# picoAva-Rev2.net
KiCad netlist of a schematic drawn in EAGLE
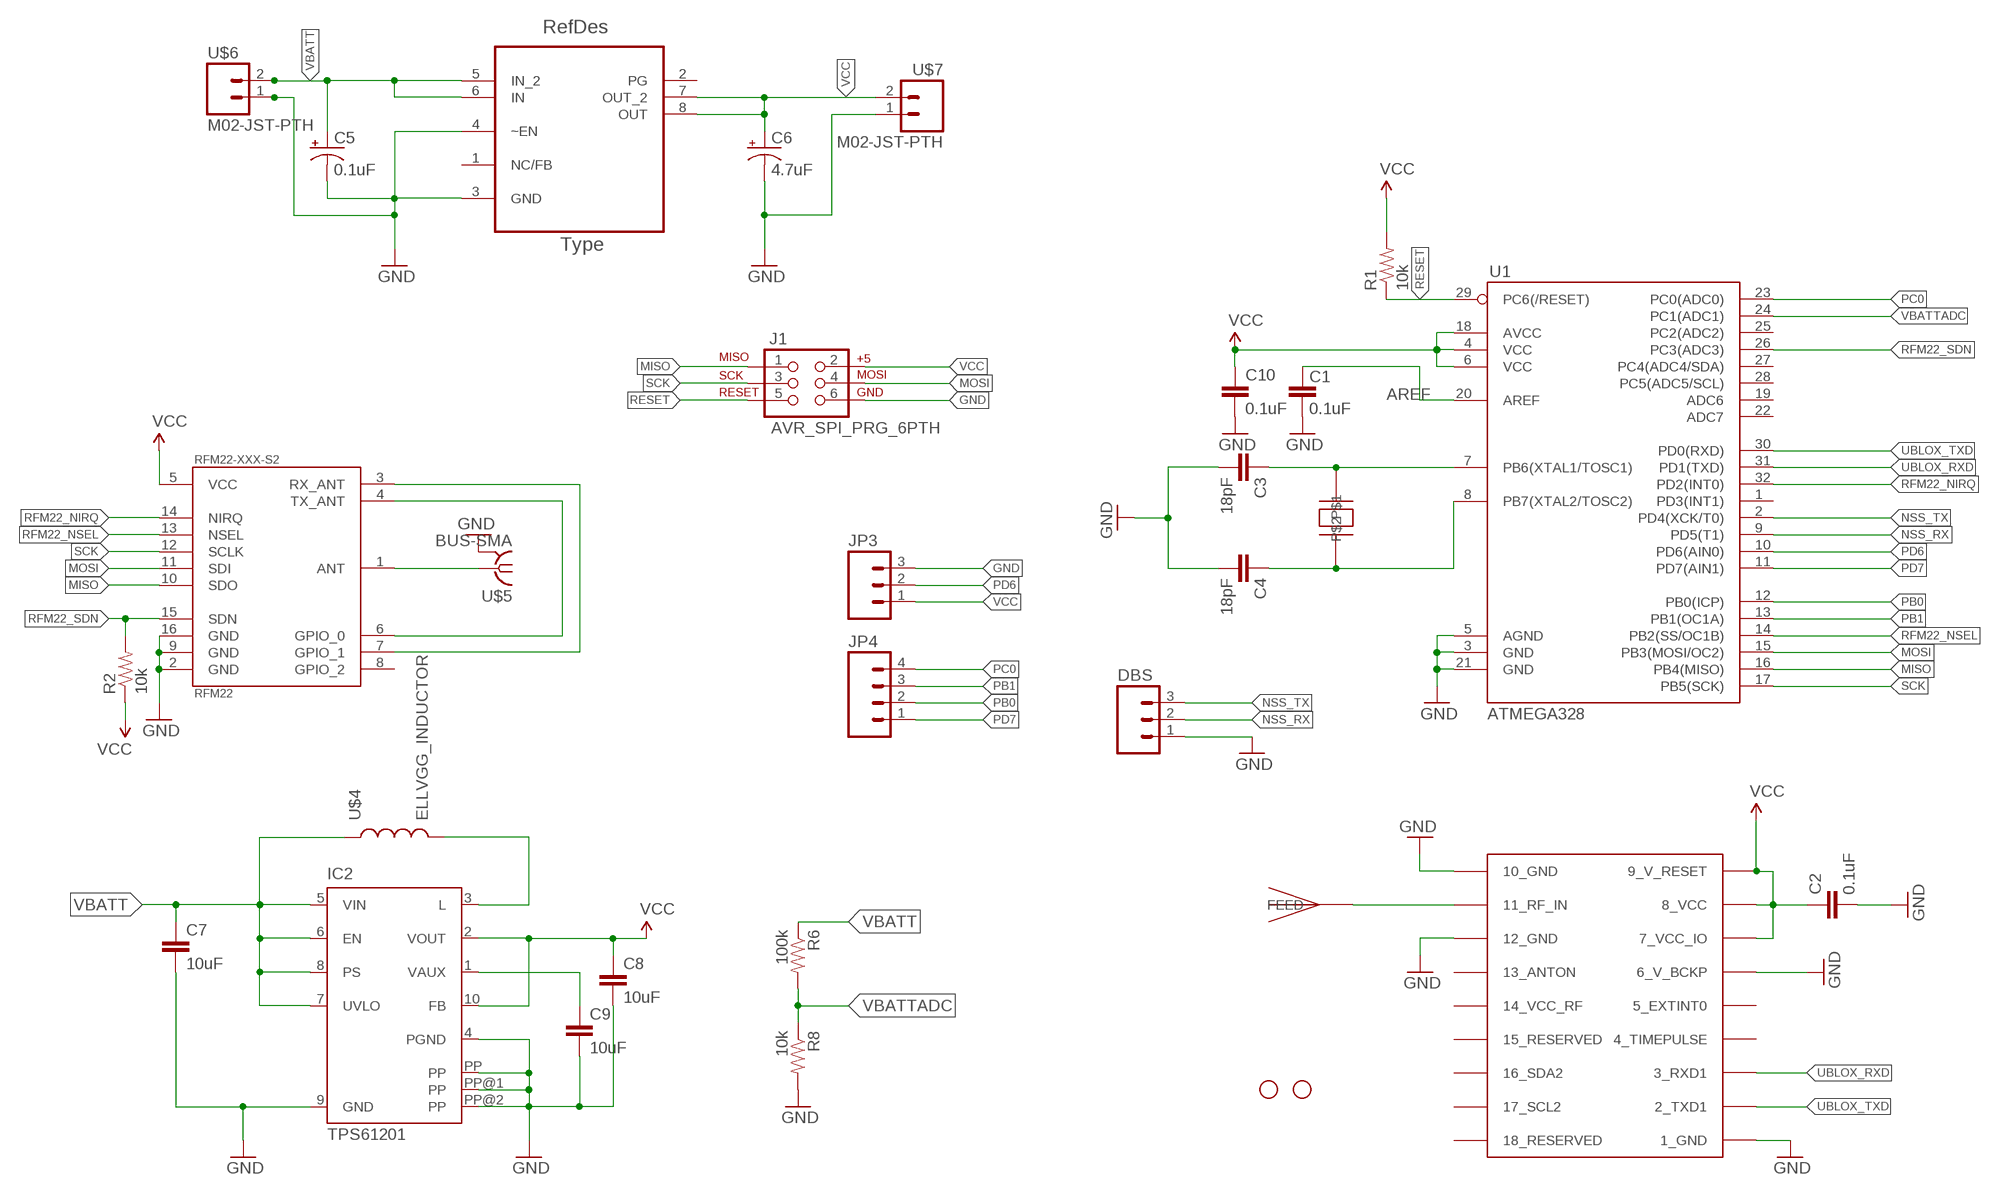
[diagram p0: schematic, sheet 1]

(export (version "E")
  (design (tool "Eeschema 10.0.6"))
  (components
    (comp (ref "C1")
      (value "0.1uF")
      (footprint "eagle-import:0402-CAP")
      (libsource (lib "eagle-import") (part "CAP0402-CAP"))
    )
    (comp (ref "C2")
      (value "0.1uF")
      (footprint "eagle-import:0402-CAP")
      (libsource (lib "eagle-import") (part "CAP0402-CAP"))
    )
    (comp (ref "C3")
      (value "18pF")
      (footprint "eagle-import:0402-CAP")
      (libsource (lib "eagle-import") (part "CAP0402-CAP"))
    )
    (comp (ref "C4")
      (value "18pF")
      (footprint "eagle-import:0402-CAP")
      (libsource (lib "eagle-import") (part "CAP0402-CAP"))
    )
    (comp (ref "C5")
      (value "0.1uF")
      (footprint "eagle-import:EIA3216-KIT")
      (libsource (lib "eagle-import") (part "CAP_POL1206-KIT"))
    )
    (comp (ref "C6")
      (value "4.7uF")
      (footprint "eagle-import:EIA3216-KIT")
      (libsource (lib "eagle-import") (part "CAP_POL1206-KIT"))
    )
    (comp (ref "C7")
      (value "10uF")
      (footprint "eagle-import:1206")
      (libsource (lib "eagle-import") (part "CAP1206"))
    )
    (comp (ref "C8")
      (value "10uF")
      (footprint "eagle-import:1206")
      (libsource (lib "eagle-import") (part "CAP1206"))
    )
    (comp (ref "C9")
      (value "10uF")
      (footprint "eagle-import:1206")
      (libsource (lib "eagle-import") (part "CAP1206"))
    )
    (comp (ref "C10")
      (value "0.1uF")
      (footprint "eagle-import:0402-CAP")
      (libsource (lib "eagle-import") (part "CAP0402-CAP"))
    )
    (comp (ref "DBS")
      (value "M03PTH")
      (footprint "eagle-import:1X03")
      (libsource (lib "eagle-import") (part "M03PTH"))
    )
    (comp (ref "IC2")
      (value "TPS61201")
      (footprint "eagle-import:S-PDSO-N10")
      (fields (field (name "MPN") "TPS61201DRCT"))
      (libsource (lib "eagle-import") (part "TPS61201"))
    )
    (comp (ref "J1")
      (value "AVR_SPI_PRG_6PTH")
      (footprint "eagle-import:2X3")
      (libsource (lib "eagle-import") (part "AVR_SPI_PRG_6PTH"))
    )
    (comp (ref "JP1")
      (value "STAND-OFF")
      (footprint "eagle-import:STAND-OFF")
      (libsource (lib "eagle-import") (part "STAND-OFF"))
    )
    (comp (ref "JP2")
      (value "STAND-OFF")
      (footprint "eagle-import:STAND-OFF")
      (libsource (lib "eagle-import") (part "STAND-OFF"))
    )
    (comp (ref "JP3")
      (value "M03PTH")
      (footprint "eagle-import:1X03")
      (libsource (lib "eagle-import") (part "M03PTH"))
    )
    (comp (ref "JP4")
      (value "M04PTH")
      (footprint "eagle-import:1X04")
      (libsource (lib "eagle-import") (part "M04PTH"))
    )
    (comp (ref "R1")
      (value "10k")
      (footprint "eagle-import:0402-RES")
      (libsource (lib "eagle-import") (part "RESISTOR0402-RES"))
    )
    (comp (ref "R2")
      (value "10k")
      (footprint "eagle-import:0402-RES")
      (libsource (lib "eagle-import") (part "RESISTOR0402-RES"))
    )
    (comp (ref "R6")
      (value "100k")
      (footprint "eagle-import:0402-RES")
      (libsource (lib "eagle-import") (part "RESISTOR0402-RES"))
    )
    (comp (ref "R8")
      (value "10k")
      (footprint "eagle-import:0402-RES")
      (libsource (lib "eagle-import") (part "RESISTOR0402-RES"))
    )
    (comp (ref "RFM22-XXX-S2")
      (value "RFM22")
      (footprint "eagle-import:RFM22-XXX-S2")
      (libsource (lib "eagle-import") (part "RFM22"))
    )
    (comp (ref "U$1")
      (value "UBLOX_MAX-6")
      (footprint "eagle-import:UBLOX_MAX-6")
      (libsource (lib "eagle-import") (part "UBLOX_MAX-6"))
    )
    (comp (ref "U$2")
      (value "ABRACON_ABM3_CRYSTAL")
      (footprint "eagle-import:ABRACON_ABM3_CRYSTAL")
      (libsource (lib "eagle-import") (part "ABRACON_ABM3_CRYSTAL"))
    )
    (comp (ref "U$3")
      (value "JTI_ANTENNA-1575AT43A40")
      (footprint "eagle-import:JTI_ANTENNA-1575AT43A40")
      (libsource (lib "eagle-import") (part "JTI_ANTENNA-1575AT43A40"))
    )
    (comp (ref "U$4")
      (value "ELLVGG_INDUCTOR")
      (footprint "eagle-import:ELLVGG_INDUCTOR")
      (libsource (lib "eagle-import") (part "ELLVGG_INDUCTOR"))
    )
    (comp (ref "U$5")
      (value "BUS-SMA")
      (footprint "eagle-import:BUS-SMA")
      (libsource (lib "eagle-import") (part "BUS-SMA"))
    )
    (comp (ref "U$6")
      (value "M02-JST-PTH")
      (footprint "eagle-import:M02-JST-PTH")
      (libsource (lib "eagle-import") (part "M02-JST-PTH"))
    )
    (comp (ref "U$7")
      (value "M02-JST-PTH")
      (footprint "eagle-import:M02-JST-PTH")
      (libsource (lib "eagle-import") (part "M02-JST-PTH"))
    )
    (comp (ref "U1")
      (value "ATMEGA328")
      (footprint "eagle-import:TQFP32-08")
      (libsource (lib "eagle-import") (part "ATMEGA168"))
    )
    (comp (ref "U2")
      (value "TPS76633D")
      (footprint "eagle-import:SOIC127P600X175-8N")
      (libsource (lib "eagle-import") (part "TPS76633D"))
    )
  )
  (nets
    (net (code "1") (name "/AREF") (class "Default")
      (node (ref "C1") (pin "2") (pinfunction "2_2") (pintype "passive"))
      (node (ref "U1") (pin "20") (pinfunction "AREF_20") (pintype "bidirectional"))
    )
    (net (code "2") (name "GND") (class "Default")
      (node (ref "C1") (pin "1") (pinfunction "1_1") (pintype "passive"))
      (node (ref "C10") (pin "2") (pinfunction "2_2") (pintype "passive"))
      (node (ref "C2") (pin "2") (pinfunction "2_2") (pintype "passive"))
      (node (ref "C3") (pin "2") (pinfunction "2_2") (pintype "passive"))
      (node (ref "C4") (pin "2") (pinfunction "2_2") (pintype "passive"))
      (node (ref "C5") (pin "C") (pinfunction "-_C") (pintype "passive"))
      (node (ref "C6") (pin "C") (pinfunction "-_C") (pintype "passive"))
      (node (ref "C7") (pin "2") (pinfunction "2_2") (pintype "passive"))
      (node (ref "C8") (pin "2") (pinfunction "2_2") (pintype "passive"))
      (node (ref "C9") (pin "2") (pinfunction "2_2") (pintype "passive"))
      (node (ref "DBS") (pin "1") (pinfunction "1_1") (pintype "passive"))
      (node (ref "IC2") (pin "4") (pinfunction "PGND_4") (pintype "power_in"))
      (node (ref "IC2") (pin "9") (pinfunction "GND_9") (pintype "power_in"))
      (node (ref "IC2") (pin "PP") (pinfunction "PP_PP") (pintype "power_in"))
      (node (ref "IC2") (pin "PP@1") (pinfunction "PP_PP@1") (pintype "power_in"))
      (node (ref "IC2") (pin "PP@2") (pinfunction "PP_PP@2") (pintype "power_in"))
      (node (ref "J1") (pin "6") (pinfunction "6_6") (pintype "passive"))
      (node (ref "JP3") (pin "3") (pinfunction "3_3") (pintype "passive"))
      (node (ref "R8") (pin "2") (pinfunction "2_2") (pintype "passive"))
      (node (ref "RFM22-XXX-S2") (pin "16") (pinfunction "GND_16") (pintype "power_in"))
      (node (ref "RFM22-XXX-S2") (pin "2") (pinfunction "GND_2") (pintype "power_in"))
      (node (ref "RFM22-XXX-S2") (pin "9") (pinfunction "GND_9") (pintype "power_in"))
      (node (ref "U$1") (pin "10_GND") (pinfunction "10_GND_10_GND") (pintype "bidirectional"))
      (node (ref "U$1") (pin "12_GND") (pinfunction "12_GND_12_GND") (pintype "bidirectional"))
      (node (ref "U$1") (pin "1_GND") (pinfunction "1_GND_1_GND") (pintype "bidirectional"))
      (node (ref "U$1") (pin "6_V_BCKP") (pinfunction "6_V_BCKP_6_V_BCKP") (pintype "bidirectional"))
      (node (ref "U$5") (pin "2") (pinfunction "GND_2") (pintype "power_in"))
      (node (ref "U$5") (pin "3") (pinfunction "GND_3") (pintype "power_in"))
      (node (ref "U$5") (pin "4") (pinfunction "GND_4") (pintype "power_in"))
      (node (ref "U$5") (pin "5") (pinfunction "GND_5") (pintype "power_in"))
      (node (ref "U$6") (pin "1") (pinfunction "1_1") (pintype "passive"))
      (node (ref "U$7") (pin "1") (pinfunction "1_1") (pintype "passive"))
      (node (ref "U1") (pin "21") (pinfunction "GND_21") (pintype "bidirectional"))
      (node (ref "U1") (pin "3") (pinfunction "GND_3") (pintype "bidirectional"))
      (node (ref "U1") (pin "5") (pinfunction "AGND_5") (pintype "bidirectional"))
      (node (ref "U2") (pin "3") (pinfunction "GND_3") (pintype "passive"))
      (node (ref "U2") (pin "4") (pinfunction "~{EN}_4") (pintype "input"))
    )
    (net (code "3") (name "MISO") (class "Default")
      (node (ref "J1") (pin "1") (pinfunction "1_1") (pintype "passive"))
      (node (ref "RFM22-XXX-S2") (pin "10") (pinfunction "SDO_10") (pintype "output"))
      (node (ref "U1") (pin "16") (pinfunction "PB4(MISO)_16") (pintype "bidirectional"))
    )
    (net (code "4") (name "MOSI") (class "Default")
      (node (ref "J1") (pin "4") (pinfunction "4_4") (pintype "passive"))
      (node (ref "RFM22-XXX-S2") (pin "11") (pinfunction "SDI_11") (pintype "input"))
      (node (ref "U1") (pin "15") (pinfunction "PB3(MOSI/OC2)_15") (pintype "bidirectional"))
    )
    (net (code "5") (name "NSS_RX") (class "Default")
      (node (ref "DBS") (pin "2") (pinfunction "2_2") (pintype "passive"))
      (node (ref "U1") (pin "9") (pinfunction "PD5(T1)_9") (pintype "bidirectional"))
    )
    (net (code "6") (name "NSS_TX") (class "Default")
      (node (ref "DBS") (pin "3") (pinfunction "3_3") (pintype "passive"))
      (node (ref "U1") (pin "2") (pinfunction "PD4(XCK/T0)_2") (pintype "bidirectional"))
    )
    (net (code "7") (name "Net-(IC2-L)") (class "Default")
      (node (ref "IC2") (pin "3") (pinfunction "L_3") (pintype "input"))
      (node (ref "U$4") (pin "P$2") (pinfunction "2_P$2") (pintype "passive"))
    )
    (net (code "8") (name "Net-(IC2-VAUX)") (class "Default")
      (node (ref "C9") (pin "1") (pinfunction "1_1") (pintype "passive"))
      (node (ref "IC2") (pin "1") (pinfunction "VAUX_1") (pintype "bidirectional"))
    )
    (net (code "9") (name "Net-(RFM22-XXX-S2-ANT)") (class "Default")
      (node (ref "RFM22-XXX-S2") (pin "1") (pinfunction "ANT_1") (pintype "bidirectional"))
      (node (ref "U$5") (pin "1") (pinfunction "1_1") (pintype "passive"))
    )
    (net (code "10") (name "Net-(RFM22-XXX-S2-GPIO_0)") (class "Default")
      (node (ref "RFM22-XXX-S2") (pin "4") (pinfunction "TX_ANT_4") (pintype "input"))
      (node (ref "RFM22-XXX-S2") (pin "6") (pinfunction "GPIO_0_6") (pintype "bidirectional"))
    )
    (net (code "11") (name "Net-(RFM22-XXX-S2-GPIO_1)") (class "Default")
      (node (ref "RFM22-XXX-S2") (pin "3") (pinfunction "RX_ANT_3") (pintype "input"))
      (node (ref "RFM22-XXX-S2") (pin "7") (pinfunction "GPIO_1_7") (pintype "bidirectional"))
    )
    (net (code "12") (name "Net-(U$1-Pad11_RF_IN)") (class "Default")
      (node (ref "U$1") (pin "11_RF_IN") (pinfunction "11_RF_IN_11_RF_IN") (pintype "bidirectional"))
      (node (ref "U$3") (pin "FEED") (pinfunction "FEED_FEED") (pintype "bidirectional"))
    )
    (net (code "13") (name "Net-(U1-PB6(XTAL1{slash}TOSC1))") (class "Default")
      (node (ref "C3") (pin "1") (pinfunction "1_1") (pintype "passive"))
      (node (ref "U$2") (pin "P$2") (pinfunction "P$2_P$2") (pintype "bidirectional"))
      (node (ref "U1") (pin "7") (pinfunction "PB6(XTAL1/TOSC1)_7") (pintype "bidirectional"))
    )
    (net (code "14") (name "Net-(U1-PB7(XTAL2{slash}TOSC2))") (class "Default")
      (node (ref "C4") (pin "1") (pinfunction "1_1") (pintype "passive"))
      (node (ref "U$2") (pin "P$1") (pinfunction "P$1_P$1") (pintype "bidirectional"))
      (node (ref "U1") (pin "8") (pinfunction "PB7(XTAL2/TOSC2)_8") (pintype "bidirectional"))
    )
    (net (code "15") (name "PB0") (class "Default")
      (node (ref "JP4") (pin "2") (pinfunction "2_2") (pintype "passive"))
      (node (ref "U1") (pin "12") (pinfunction "PB0(ICP)_12") (pintype "bidirectional"))
    )
    (net (code "16") (name "PB1") (class "Default")
      (node (ref "JP4") (pin "3") (pinfunction "3_3") (pintype "passive"))
      (node (ref "U1") (pin "13") (pinfunction "PB1(OC1A)_13") (pintype "bidirectional"))
    )
    (net (code "17") (name "PC0") (class "Default")
      (node (ref "JP4") (pin "4") (pinfunction "4_4") (pintype "passive"))
      (node (ref "U1") (pin "23") (pinfunction "PC0(ADC0)_23") (pintype "bidirectional"))
    )
    (net (code "18") (name "PD6") (class "Default")
      (node (ref "JP3") (pin "2") (pinfunction "2_2") (pintype "passive"))
      (node (ref "U1") (pin "10") (pinfunction "PD6(AIN0)_10") (pintype "bidirectional"))
    )
    (net (code "19") (name "PD7") (class "Default")
      (node (ref "JP4") (pin "1") (pinfunction "1_1") (pintype "passive"))
      (node (ref "U1") (pin "11") (pinfunction "PD7(AIN1)_11") (pintype "bidirectional"))
    )
    (net (code "20") (name "RESET") (class "Default")
      (node (ref "J1") (pin "5") (pinfunction "5_5") (pintype "passive"))
      (node (ref "R1") (pin "1") (pinfunction "1_1") (pintype "passive"))
      (node (ref "U1") (pin "29") (pinfunction "PC6(/RESET)_29") (pintype "bidirectional"))
    )
    (net (code "21") (name "RFM22_NIRQ") (class "Default")
      (node (ref "RFM22-XXX-S2") (pin "14") (pinfunction "NIRQ_14") (pintype "output"))
      (node (ref "U1") (pin "32") (pinfunction "PD2(INT0)_32") (pintype "bidirectional"))
    )
    (net (code "22") (name "RFM22_NSEL") (class "Default")
      (node (ref "RFM22-XXX-S2") (pin "13") (pinfunction "NSEL_13") (pintype "input"))
      (node (ref "U1") (pin "14") (pinfunction "PB2(SS/OC1B)_14") (pintype "bidirectional"))
    )
    (net (code "23") (name "RFM22_SDN") (class "Default")
      (node (ref "R2") (pin "2") (pinfunction "2_2") (pintype "passive"))
      (node (ref "RFM22-XXX-S2") (pin "15") (pinfunction "SDN_15") (pintype "input"))
      (node (ref "U1") (pin "26") (pinfunction "PC3(ADC3)_26") (pintype "bidirectional"))
    )
    (net (code "24") (name "SCK") (class "Default")
      (node (ref "J1") (pin "3") (pinfunction "3_3") (pintype "passive"))
      (node (ref "RFM22-XXX-S2") (pin "12") (pinfunction "SCLK_12") (pintype "input"))
      (node (ref "U1") (pin "17") (pinfunction "PB5(SCK)_17") (pintype "bidirectional"))
    )
    (net (code "25") (name "UBLOX_RXD") (class "Default")
      (node (ref "U$1") (pin "3_RXD1") (pinfunction "3_RXD1_3_RXD1") (pintype "bidirectional"))
      (node (ref "U1") (pin "31") (pinfunction "PD1(TXD)_31") (pintype "bidirectional"))
    )
    (net (code "26") (name "UBLOX_TXD") (class "Default")
      (node (ref "U$1") (pin "2_TXD1") (pinfunction "2_TXD1_2_TXD1") (pintype "bidirectional"))
      (node (ref "U1") (pin "30") (pinfunction "PD0(RXD)_30") (pintype "bidirectional"))
    )
    (net (code "27") (name "VBATT") (class "Default")
      (node (ref "C5") (pin "A") (pinfunction "+_A") (pintype "passive"))
      (node (ref "C7") (pin "1") (pinfunction "1_1") (pintype "passive"))
      (node (ref "IC2") (pin "5") (pinfunction "VIN_5") (pintype "input"))
      (node (ref "IC2") (pin "6") (pinfunction "EN_6") (pintype "input"))
      (node (ref "IC2") (pin "7") (pinfunction "UVLO_7") (pintype "input"))
      (node (ref "IC2") (pin "8") (pinfunction "PS_8") (pintype "input"))
      (node (ref "R6") (pin "1") (pinfunction "1_1") (pintype "passive"))
      (node (ref "U$4") (pin "P$1") (pinfunction "1_P$1") (pintype "passive"))
      (node (ref "U$6") (pin "2") (pinfunction "2_2") (pintype "passive"))
      (node (ref "U2") (pin "5") (pinfunction "IN_2_5") (pintype "input"))
      (node (ref "U2") (pin "6") (pinfunction "IN_6") (pintype "input"))
    )
    (net (code "28") (name "VBATTADC") (class "Default")
      (node (ref "R6") (pin "2") (pinfunction "2_2") (pintype "passive"))
      (node (ref "R8") (pin "1") (pinfunction "1_1") (pintype "passive"))
      (node (ref "U1") (pin "24") (pinfunction "PC1(ADC1)_24") (pintype "bidirectional"))
    )
    (net (code "29") (name "VCC") (class "Default")
      (node (ref "C10") (pin "1") (pinfunction "1_1") (pintype "passive"))
      (node (ref "C2") (pin "1") (pinfunction "1_1") (pintype "passive"))
      (node (ref "C6") (pin "A") (pinfunction "+_A") (pintype "passive"))
      (node (ref "C8") (pin "1") (pinfunction "1_1") (pintype "passive"))
      (node (ref "IC2") (pin "10") (pinfunction "FB_10") (pintype "input"))
      (node (ref "IC2") (pin "2") (pinfunction "VOUT_2") (pintype "passive"))
      (node (ref "J1") (pin "2") (pinfunction "2_2") (pintype "passive"))
      (node (ref "JP3") (pin "1") (pinfunction "1_1") (pintype "passive"))
      (node (ref "R1") (pin "2") (pinfunction "2_2") (pintype "passive"))
      (node (ref "R2") (pin "1") (pinfunction "1_1") (pintype "passive"))
      (node (ref "RFM22-XXX-S2") (pin "5") (pinfunction "VCC_5") (pintype "bidirectional"))
      (node (ref "U$1") (pin "7_VCC_IO") (pinfunction "7_VCC_IO_7_VCC_IO") (pintype "bidirectional"))
      (node (ref "U$1") (pin "8_VCC") (pinfunction "8_VCC_8_VCC") (pintype "bidirectional"))
      (node (ref "U$1") (pin "9_V_RESET") (pinfunction "9_V_RESET_9_V_RESET") (pintype "bidirectional"))
      (node (ref "U$7") (pin "2") (pinfunction "2_2") (pintype "passive"))
      (node (ref "U1") (pin "18") (pinfunction "AVCC_18") (pintype "bidirectional"))
      (node (ref "U1") (pin "4") (pinfunction "VCC_4") (pintype "bidirectional"))
      (node (ref "U1") (pin "6") (pinfunction "VCC_6") (pintype "bidirectional"))
      (node (ref "U2") (pin "7") (pinfunction "OUT_2_7") (pintype "output"))
      (node (ref "U2") (pin "8") (pinfunction "OUT_8") (pintype "output"))
    )
    (net (code "30") (name "unconnected-(RFM22-XXX-S2-GPIO_2-Pad8)") (class "Default")
      (node (ref "RFM22-XXX-S2") (pin "8") (pinfunction "GPIO_2_8") (pintype "bidirectional"))
    )
    (net (code "31") (name "unconnected-(U$1-Pad4_TIMEPULSE)") (class "Default")
      (node (ref "U$1") (pin "4_TIMEPULSE") (pinfunction "4_TIMEPULSE_4_TIMEPULSE") (pintype "bidirectional"))
    )
    (net (code "32") (name "unconnected-(U$1-Pad5_EXTINT0)") (class "Default")
      (node (ref "U$1") (pin "5_EXTINT0") (pinfunction "5_EXTINT0_5_EXTINT0") (pintype "bidirectional"))
    )
    (net (code "33") (name "unconnected-(U$1-Pad13_ANTON)") (class "Default")
      (node (ref "U$1") (pin "13_ANTON") (pinfunction "13_ANTON_13_ANTON") (pintype "bidirectional"))
    )
    (net (code "34") (name "unconnected-(U$1-Pad14_VCC_RF)") (class "Default")
      (node (ref "U$1") (pin "14_VCC_RF") (pinfunction "14_VCC_RF_14_VCC_RF") (pintype "bidirectional"))
    )
    (net (code "35") (name "unconnected-(U$1-Pad15_RESERVED)") (class "Default")
      (node (ref "U$1") (pin "15_RESERVED") (pinfunction "15_RESERVED_15_RESERVED") (pintype "bidirectional"))
    )
    (net (code "36") (name "unconnected-(U$1-Pad16_SDA2)") (class "Default")
      (node (ref "U$1") (pin "16_SDA2") (pinfunction "16_SDA2_16_SDA2") (pintype "bidirectional"))
    )
    (net (code "37") (name "unconnected-(U$1-Pad17_SCL2)") (class "Default")
      (node (ref "U$1") (pin "17_SCL2") (pinfunction "17_SCL2_17_SCL2") (pintype "bidirectional"))
    )
    (net (code "38") (name "unconnected-(U$1-Pad18_RESERVED)") (class "Default")
      (node (ref "U$1") (pin "18_RESERVED") (pinfunction "18_RESERVED_18_RESERVED") (pintype "bidirectional"))
    )
    (net (code "39") (name "unconnected-(U1-ADC6-Pad19)") (class "Default")
      (node (ref "U1") (pin "19") (pinfunction "ADC6_19") (pintype "bidirectional"))
    )
    (net (code "40") (name "unconnected-(U1-ADC7-Pad22)") (class "Default")
      (node (ref "U1") (pin "22") (pinfunction "ADC7_22") (pintype "bidirectional"))
    )
    (net (code "41") (name "unconnected-(U1-PC2(ADC2)-Pad25)") (class "Default")
      (node (ref "U1") (pin "25") (pinfunction "PC2(ADC2)_25") (pintype "bidirectional"))
    )
    (net (code "42") (name "unconnected-(U1-PC4(ADC4{slash}SDA)-Pad27)") (class "Default")
      (node (ref "U1") (pin "27") (pinfunction "PC4(ADC4/SDA)_27") (pintype "bidirectional"))
    )
    (net (code "43") (name "unconnected-(U1-PC5(ADC5{slash}SCL)-Pad28)") (class "Default")
      (node (ref "U1") (pin "28") (pinfunction "PC5(ADC5/SCL)_28") (pintype "bidirectional"))
    )
    (net (code "44") (name "unconnected-(U1-PD3(INT1)-Pad1)") (class "Default")
      (node (ref "U1") (pin "1") (pinfunction "PD3(INT1)_1") (pintype "bidirectional"))
    )
    (net (code "45") (name "unconnected-(U2-NC{slash}FB-Pad1)") (class "Default")
      (node (ref "U2") (pin "1") (pinfunction "NC/FB_1") (pintype "no_connect"))
    )
    (net (code "46") (name "unconnected-(U2-PG-Pad2)") (class "Default")
      (node (ref "U2") (pin "2") (pinfunction "PG_2") (pintype "output"))
    )
  )
)
